# USBC.net
KiCad netlist of a schematic drawn in Altium Designer
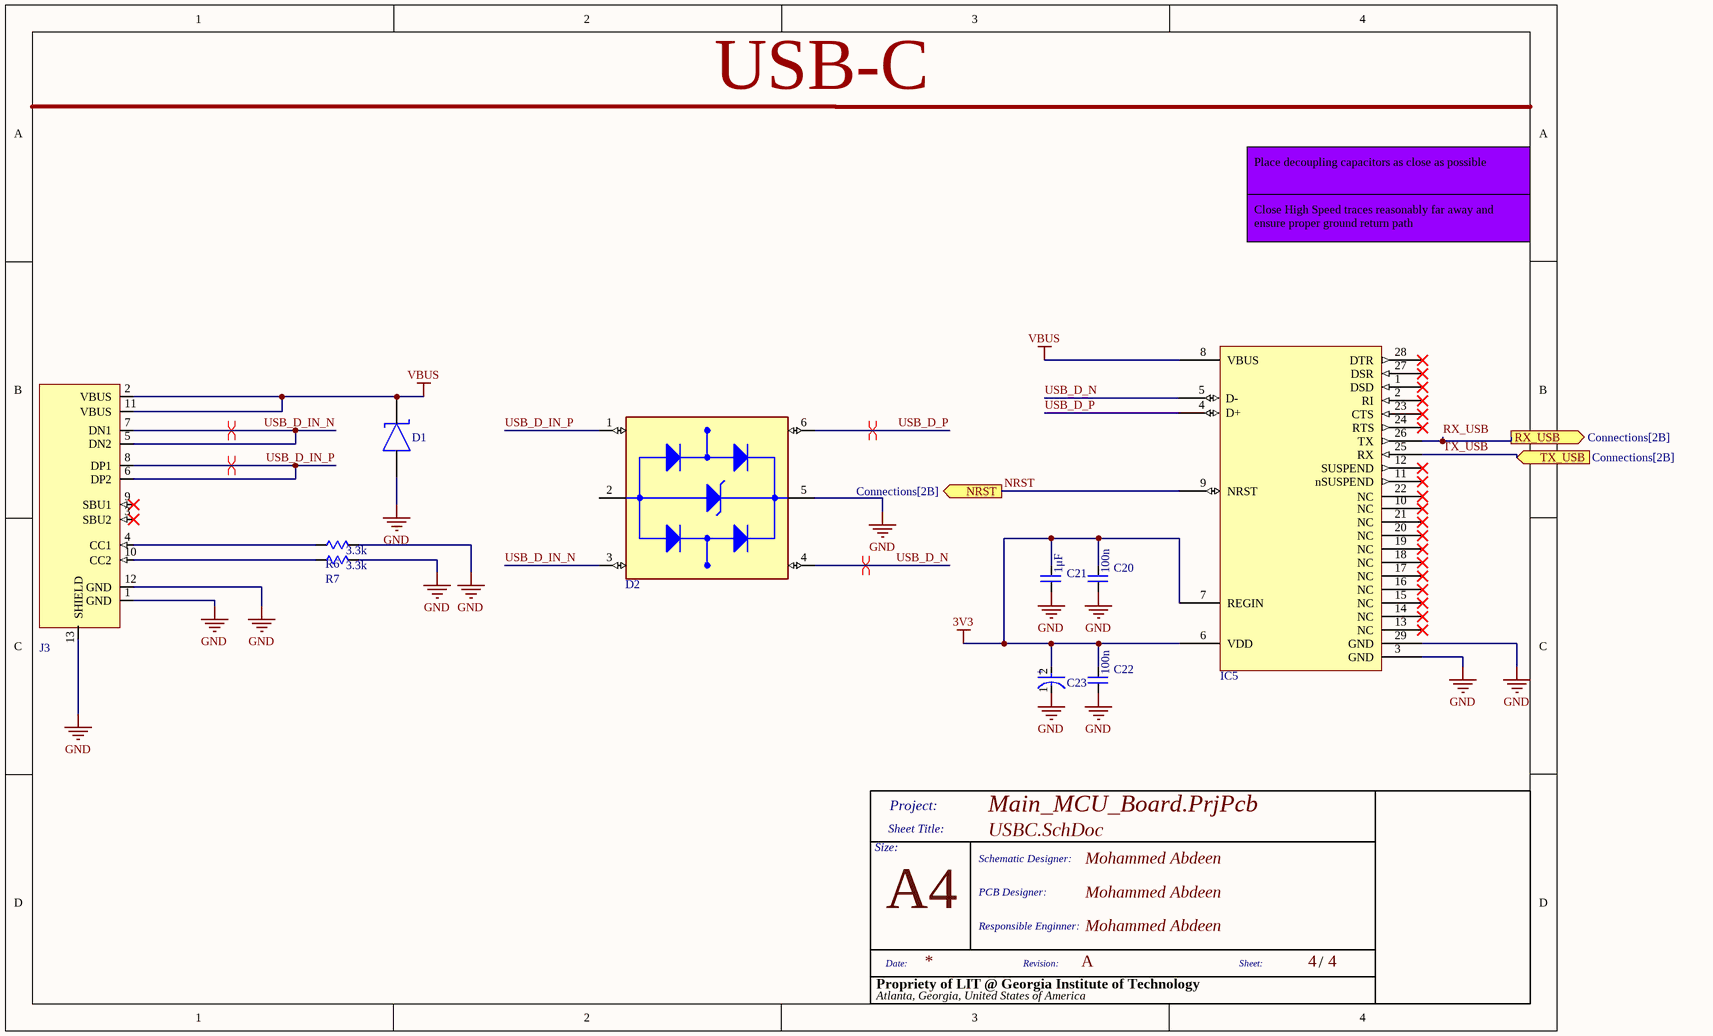
[diagram p0: USBC.SchDoc]

(export (version "E")
  (design (tool "Eeschema 10.0.6"))
  (components
    (comp (ref "C20")
      (value "KGM21NR71E104KT")
      (footprint "0805-RES")
      (description "0.1 µF ±10% 25V Ceramic Capacitor X7R 0805 (2012 Metric)")
      (libsource (lib "MySchLib") (part "CAP-0805-25V-100n"))
    )
    (comp (ref "C21")
      (value "C0603C105Z8VAC7867")
      (footprint "0603-CAP")
      (description "1 µF -20%, +80% 10V Ceramic Capacitor Y5V (F) 0603 (1608 Metric)")
      (libsource (lib "MySchLib") (part "CAP-0603-10V-1uF"))
    )
    (comp (ref "C22")
      (value "KGM21NR71E104KT")
      (footprint "0805-RES")
      (description "0.1 µF ±10% 25V Ceramic Capacitor X7R 0805 (2012 Metric)")
      (libsource (lib "MySchLib") (part "CAP-0805-25V-100n"))
    )
    (comp (ref "C23")
      (value "865080640004")
      (footprint "865080640004")
      (description "4.7 µF 50 V Aluminum Electrolytic Capacitors Radial, Can - SMD 2000 Hrs @ 105°C")
      (libsource (lib "MySchLib") (part "CAP-RADIALSMD-4.7uF(BIAS)"))
    )
    (comp (ref "D1")
      (value "PESD5V0X1UB,135")
      (footprint "PESD5V0X1UB,135")
      (description "8V (Typ) Clamp 1.5A (8/20µs) Ipp Tvs Diode Surface Mount SOD-523")
      (libsource (lib "MainMCUSch") (part "TVS-8V-5.8V"))
    )
    (comp (ref "D2")
      (value "USBLC6-2SC6")
      (footprint "SOT95P280X145-6N")
      (description "17V Clamp 5A (8/20µs) Ipp Tvs Diode Surface Mount SOT-23-6")
      (libsource (lib "MainMCUSch") (part "TVS-6V-17V"))
    )
    (comp (ref "IC5")
      (value "CP2102-GMR")
      (footprint "28-VFQFN")
      (description "USB Bridge, USB to UART USB 2.0 UART Interface 28-QFN (5x5)")
      (fields (field (name "MANUFACTURER") "Silicon Labs"))
      (libsource (lib "MainMCUSch") (part "USbtoUART"))
    )
    (comp (ref "J3")
      (value "USB4105-GF-A")
      (footprint "USB4105-GF-A")
      (fields (field (name "MANUFACTURER") "GCT"))
      (libsource (lib "MainMCUSch") (part "USB C"))
    )
    (comp (ref "R6")
      (value "ERA-3AEB332V")
      (footprint "0603-RES")
      (description "3.3 kOhms ±0.1% 0.1W, 1/10W Chip Resistor 0603 (1608 Metric) Automotive AEC-Q200 Thin Film")
      (fields (field (name "MANUFACTURER") "Panasonic Electronic Components"))
      (libsource (lib "MainMCUSch") (part "RES-0603-3.3k"))
    )
    (comp (ref "R7")
      (value "ERA-3AEB332V")
      (footprint "0603-RES")
      (description "3.3 kOhms ±0.1% 0.1W, 1/10W Chip Resistor 0603 (1608 Metric) Automotive AEC-Q200 Thin Film")
      (fields (field (name "MANUFACTURER") "Panasonic Electronic Components"))
      (libsource (lib "MainMCUSch") (part "RES-0603-3.3k"))
    )
  )
  (nets
    (net (code "1") (name "/NRST") (class "Default")
      (node (ref "IC5") (pin "9") (pinfunction "NRST_9") (pintype "bidirectional"))
    )
    (net (code "2") (name "/RX_USB") (class "Default")
      (node (ref "IC5") (pin "26") (pinfunction "TX_26") (pintype "output"))
    )
    (net (code "3") (name "/TX_USB") (class "Default")
      (node (ref "IC5") (pin "25") (pinfunction "RX_25") (pintype "input"))
    )
    (net (code "4") (name "/USB_D_IN_N") (class "Default")
      (node (ref "D2") (pin "3") (pinfunction "I/O2_IN_3") (pintype "bidirectional"))
      (node (ref "J3") (pin "5") (pinfunction "DN2_5") (pintype "bidirectional"))
      (node (ref "J3") (pin "7") (pinfunction "DN1_7") (pintype "bidirectional"))
    )
    (net (code "5") (name "/USB_D_IN_P") (class "Default")
      (node (ref "D2") (pin "1") (pinfunction "I/O1_IN_1") (pintype "bidirectional"))
      (node (ref "J3") (pin "6") (pinfunction "DP2_6") (pintype "bidirectional"))
      (node (ref "J3") (pin "8") (pinfunction "DP1_8") (pintype "bidirectional"))
    )
    (net (code "6") (name "/USB_D_N") (class "Default")
      (node (ref "D2") (pin "4") (pinfunction "I/O2_OUT_4") (pintype "bidirectional"))
      (node (ref "IC5") (pin "5") (pinfunction "D-_5") (pintype "bidirectional"))
    )
    (net (code "7") (name "/USB_D_P") (class "Default")
      (node (ref "D2") (pin "6") (pinfunction "I/O1_OUT_6") (pintype "bidirectional"))
      (node (ref "IC5") (pin "4") (pinfunction "D+_4") (pintype "bidirectional"))
    )
    (net (code "8") (name "3V3") (class "Default")
      (node (ref "C20") (pin "2") (pintype "passive"))
      (node (ref "C21") (pin "2") (pintype "passive"))
      (node (ref "C22") (pin "2") (pintype "passive"))
      (node (ref "C23") (pin "2") (pinfunction "A_2") (pintype "passive"))
      (node (ref "IC5") (pin "6") (pinfunction "VDD_6") (pintype "power_in"))
      (node (ref "IC5") (pin "7") (pinfunction "REGIN_7") (pintype "power_in"))
    )
    (net (code "9") (name "GND") (class "Default")
      (node (ref "C20") (pin "1") (pintype "passive"))
      (node (ref "C21") (pin "1") (pintype "passive"))
      (node (ref "C22") (pin "1") (pintype "passive"))
      (node (ref "C23") (pin "1") (pinfunction "C_1") (pintype "passive"))
      (node (ref "D1") (pin "1") (pintype "passive"))
      (node (ref "D2") (pin "5") (pinfunction "VBUS_5") (pintype "power_in"))
      (node (ref "IC5") (pin "29") (pinfunction "GND_29") (pintype "power_in"))
      (node (ref "IC5") (pin "3") (pinfunction "GND_3") (pintype "power_in"))
      (node (ref "J3") (pin "1") (pinfunction "GND_1") (pintype "power_in"))
      (node (ref "J3") (pin "12") (pinfunction "GND_12") (pintype "power_in"))
      (node (ref "J3") (pin "13") (pinfunction "SHIELD_13") (pintype "power_in"))
      (node (ref "R6") (pin "2") (pintype "passive"))
      (node (ref "R7") (pin "2") (pintype "passive"))
    )
    (net (code "10") (name "Net-(J3-CC1)") (class "Default")
      (node (ref "J3") (pin "4") (pinfunction "CC1_4") (pintype "input"))
      (node (ref "R6") (pin "1") (pintype "passive"))
    )
    (net (code "11") (name "Net-(J3-CC2)") (class "Default")
      (node (ref "J3") (pin "10") (pinfunction "CC2_10") (pintype "input"))
      (node (ref "R7") (pin "1") (pintype "passive"))
    )
    (net (code "12") (name "VBUS") (class "Default")
      (node (ref "D1") (pin "2") (pintype "passive"))
      (node (ref "IC5") (pin "8") (pinfunction "VBUS_8") (pintype "power_in"))
      (node (ref "J3") (pin "11") (pinfunction "VBUS_11") (pintype "power_in"))
      (node (ref "J3") (pin "2") (pinfunction "VBUS_2") (pintype "power_in"))
    )
    (net (code "13") (name "unconnected-(D2-GND-Pad2)") (class "Default")
      (node (ref "D2") (pin "2") (pinfunction "GND_2") (pintype "power_in"))
    )
    (net (code "14") (name "unconnected-(IC5-CTS-Pad23)") (class "Default")
      (node (ref "IC5") (pin "23") (pinfunction "CTS_23") (pintype "input+no_connect"))
    )
    (net (code "15") (name "unconnected-(IC5-DSD-Pad1)") (class "Default")
      (node (ref "IC5") (pin "1") (pinfunction "DSD_1") (pintype "input+no_connect"))
    )
    (net (code "16") (name "unconnected-(IC5-DSR-Pad27)") (class "Default")
      (node (ref "IC5") (pin "27") (pinfunction "DSR_27") (pintype "input+no_connect"))
    )
    (net (code "17") (name "unconnected-(IC5-DTR-Pad28)") (class "Default")
      (node (ref "IC5") (pin "28") (pinfunction "DTR_28") (pintype "output+no_connect"))
    )
    (net (code "18") (name "unconnected-(IC5-NC-Pad10)") (class "Default")
      (node (ref "IC5") (pin "10") (pinfunction "NC_10") (pintype "passive+no_connect"))
    )
    (net (code "19") (name "unconnected-(IC5-NC-Pad13)") (class "Default")
      (node (ref "IC5") (pin "13") (pinfunction "NC_13") (pintype "passive+no_connect"))
    )
    (net (code "20") (name "unconnected-(IC5-NC-Pad14)") (class "Default")
      (node (ref "IC5") (pin "14") (pinfunction "NC_14") (pintype "passive+no_connect"))
    )
    (net (code "21") (name "unconnected-(IC5-NC-Pad15)") (class "Default")
      (node (ref "IC5") (pin "15") (pinfunction "NC_15") (pintype "passive+no_connect"))
    )
    (net (code "22") (name "unconnected-(IC5-NC-Pad16)") (class "Default")
      (node (ref "IC5") (pin "16") (pinfunction "NC_16") (pintype "passive+no_connect"))
    )
    (net (code "23") (name "unconnected-(IC5-NC-Pad17)") (class "Default")
      (node (ref "IC5") (pin "17") (pinfunction "NC_17") (pintype "passive+no_connect"))
    )
    (net (code "24") (name "unconnected-(IC5-NC-Pad18)") (class "Default")
      (node (ref "IC5") (pin "18") (pinfunction "NC_18") (pintype "passive+no_connect"))
    )
    (net (code "25") (name "unconnected-(IC5-NC-Pad19)") (class "Default")
      (node (ref "IC5") (pin "19") (pinfunction "NC_19") (pintype "passive+no_connect"))
    )
    (net (code "26") (name "unconnected-(IC5-NC-Pad20)") (class "Default")
      (node (ref "IC5") (pin "20") (pinfunction "NC_20") (pintype "passive+no_connect"))
    )
    (net (code "27") (name "unconnected-(IC5-NC-Pad21)") (class "Default")
      (node (ref "IC5") (pin "21") (pinfunction "NC_21") (pintype "passive+no_connect"))
    )
    (net (code "28") (name "unconnected-(IC5-NC-Pad22)") (class "Default")
      (node (ref "IC5") (pin "22") (pinfunction "NC_22") (pintype "passive+no_connect"))
    )
    (net (code "29") (name "unconnected-(IC5-RI-Pad2)") (class "Default")
      (node (ref "IC5") (pin "2") (pinfunction "RI_2") (pintype "input+no_connect"))
    )
    (net (code "30") (name "unconnected-(IC5-RTS-Pad24)") (class "Default")
      (node (ref "IC5") (pin "24") (pinfunction "RTS_24") (pintype "output+no_connect"))
    )
    (net (code "31") (name "unconnected-(IC5-SUSPEND-Pad12)") (class "Default")
      (node (ref "IC5") (pin "12") (pinfunction "SUSPEND_12") (pintype "output+no_connect"))
    )
    (net (code "32") (name "unconnected-(IC5-nSUSPEND-Pad11)") (class "Default")
      (node (ref "IC5") (pin "11") (pinfunction "nSUSPEND_11") (pintype "output+no_connect"))
    )
    (net (code "33") (name "unconnected-(J3-SBU1-Pad9)") (class "Default")
      (node (ref "J3") (pin "9") (pinfunction "SBU1_9") (pintype "input+no_connect"))
    )
    (net (code "34") (name "unconnected-(J3-SBU2-Pad3)") (class "Default")
      (node (ref "J3") (pin "3") (pinfunction "SBU2_3") (pintype "input+no_connect"))
    )
  )
)
